# eRIC_breakout.net
KiCad netlist of a schematic drawn in EAGLE
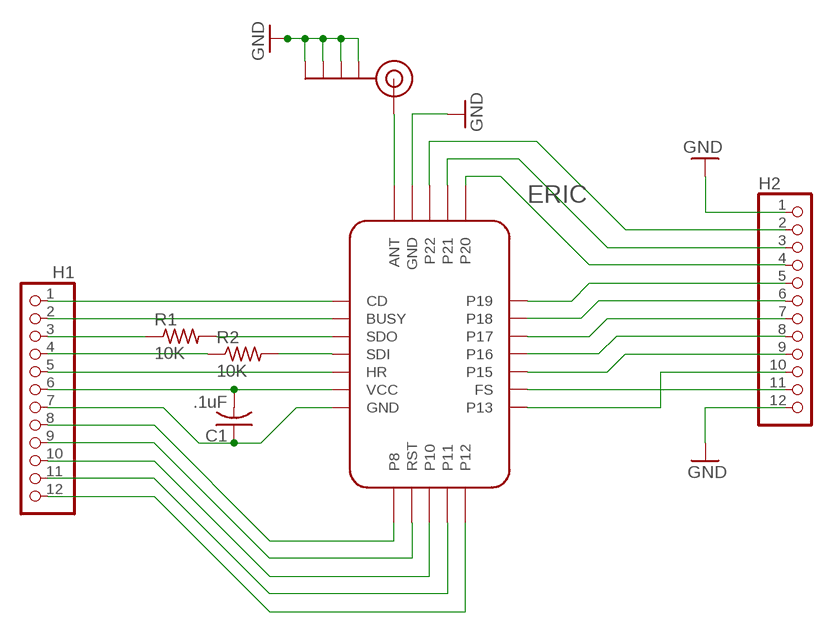
[diagram p0: schematic, sheet 1]

(export (version "E")
  (design (tool "Eeschema 10.0.6"))
  (components
    (comp (ref "C1")
      (value ".1uF")
      (footprint "eagle-import:C0603K")
      (libsource (lib "eagle-import") (part "C-USC0603K"))
    )
    (comp (ref "ERIC")
      (value "ERIC")
      (footprint "eagle-import:ERIC")
      (libsource (lib "eagle-import") (part "ERIC"))
    )
    (comp (ref "H1")
      (value "PINHD-1X12-CB")
      (footprint "eagle-import:1X12-CB")
      (libsource (lib "eagle-import") (part "PINHD-1X12-CB"))
    )
    (comp (ref "H2")
      (value "PINHD-1X12-CB")
      (footprint "eagle-import:1X12-CB")
      (libsource (lib "eagle-import") (part "PINHD-1X12-CB"))
    )
    (comp (ref "J$1")
      (value "SMA_EDGE")
      (footprint "eagle-import:SMA-EDGE")
      (libsource (lib "eagle-import") (part "SMA_EDGE"))
    )
    (comp (ref "R1")
      (value "10K")
      (footprint "eagle-import:R0603")
      (libsource (lib "eagle-import") (part "R-US_R0603"))
    )
    (comp (ref "R2")
      (value "10K")
      (footprint "eagle-import:R0603")
      (libsource (lib "eagle-import") (part "R-US_R0603"))
    )
  )
  (nets
    (net (code "1") (name "/SDI") (class "Default")
      (node (ref "ERIC") (pin "SDI") (pinfunction "SDI_SDI") (pintype "bidirectional"))
      (node (ref "H1") (pin "4") (pinfunction "4_4") (pintype "passive"))
      (node (ref "R2") (pin "1") (pinfunction "1_1") (pintype "passive"))
      (node (ref "R2") (pin "2") (pinfunction "2_2") (pintype "passive"))
    )
    (net (code "2") (name "/SDO") (class "Default")
      (node (ref "ERIC") (pin "SDO") (pinfunction "SDO_SDO") (pintype "bidirectional"))
      (node (ref "H1") (pin "3") (pinfunction "3_3") (pintype "passive"))
      (node (ref "R1") (pin "1") (pinfunction "1_1") (pintype "passive"))
      (node (ref "R1") (pin "2") (pinfunction "2_2") (pintype "passive"))
    )
    (net (code "3") (name "GND") (class "Default")
      (node (ref "C1") (pin "1") (pinfunction "1_1") (pintype "passive"))
      (node (ref "ERIC") (pin "AGND") (pinfunction "GND_AGND") (pintype "bidirectional"))
      (node (ref "ERIC") (pin "GND") (pinfunction "GND_GND") (pintype "power_in"))
      (node (ref "H1") (pin "7") (pinfunction "7_7") (pintype "passive"))
      (node (ref "H2") (pin "1") (pinfunction "1_1") (pintype "passive"))
      (node (ref "H2") (pin "12") (pinfunction "12_12") (pintype "passive"))
      (node (ref "J$1") (pin "GND@0") (pinfunction "GND_GND@0") (pintype "bidirectional"))
      (node (ref "J$1") (pin "GND@1") (pinfunction "GND_GND@1") (pintype "bidirectional"))
      (node (ref "J$1") (pin "GND@2") (pinfunction "GND_GND@2") (pintype "bidirectional"))
      (node (ref "J$1") (pin "GND@3") (pinfunction "GND_GND@3") (pintype "bidirectional"))
    )
    (net (code "4") (name "Net-(C1-Pad2)") (class "Default")
      (node (ref "C1") (pin "2") (pinfunction "2_2") (pintype "passive"))
      (node (ref "ERIC") (pin "VCC") (pinfunction "VCC_VCC") (pintype "power_in"))
      (node (ref "H1") (pin "6") (pinfunction "6_6") (pintype "passive"))
    )
    (net (code "5") (name "Net-(ERIC-P8)") (class "Default")
      (node (ref "ERIC") (pin "E8") (pinfunction "P8_E8") (pintype "bidirectional"))
      (node (ref "H1") (pin "8") (pinfunction "8_8") (pintype "passive"))
    )
    (net (code "6") (name "Net-(ERIC-P10)") (class "Default")
      (node (ref "ERIC") (pin "E10") (pinfunction "P10_E10") (pintype "bidirectional"))
      (node (ref "H1") (pin "10") (pinfunction "10_10") (pintype "passive"))
    )
    (net (code "7") (name "Net-(ERIC-P11)") (class "Default")
      (node (ref "ERIC") (pin "E11") (pinfunction "P11_E11") (pintype "bidirectional"))
      (node (ref "H1") (pin "11") (pinfunction "11_11") (pintype "passive"))
    )
    (net (code "8") (name "Net-(ERIC-P12)") (class "Default")
      (node (ref "ERIC") (pin "E12") (pinfunction "P12_E12") (pintype "bidirectional"))
      (node (ref "H1") (pin "12") (pinfunction "12_12") (pintype "passive"))
    )
    (net (code "9") (name "Net-(ERIC-P13)") (class "Default")
      (node (ref "ERIC") (pin "E13") (pinfunction "P13_E13") (pintype "bidirectional"))
      (node (ref "H2") (pin "10") (pinfunction "10_10") (pintype "passive"))
    )
    (net (code "10") (name "Net-(ERIC-P15)") (class "Default")
      (node (ref "ERIC") (pin "E15") (pinfunction "P15_E15") (pintype "bidirectional"))
      (node (ref "H2") (pin "9") (pinfunction "9_9") (pintype "passive"))
    )
    (net (code "11") (name "Net-(ERIC-P16)") (class "Default")
      (node (ref "ERIC") (pin "E16") (pinfunction "P16_E16") (pintype "bidirectional"))
      (node (ref "H2") (pin "8") (pinfunction "8_8") (pintype "passive"))
    )
    (net (code "12") (name "Net-(ERIC-P17)") (class "Default")
      (node (ref "ERIC") (pin "E17") (pinfunction "P17_E17") (pintype "bidirectional"))
      (node (ref "H2") (pin "7") (pinfunction "7_7") (pintype "passive"))
    )
    (net (code "13") (name "Net-(ERIC-P18)") (class "Default")
      (node (ref "ERIC") (pin "E18") (pinfunction "P18_E18") (pintype "bidirectional"))
      (node (ref "H2") (pin "6") (pinfunction "6_6") (pintype "passive"))
    )
    (net (code "14") (name "Net-(ERIC-P19)") (class "Default")
      (node (ref "ERIC") (pin "E19") (pinfunction "P19_E19") (pintype "bidirectional"))
      (node (ref "H2") (pin "5") (pinfunction "5_5") (pintype "passive"))
    )
    (net (code "15") (name "Net-(ERIC-P20)") (class "Default")
      (node (ref "ERIC") (pin "E20") (pinfunction "P20_E20") (pintype "bidirectional"))
      (node (ref "H2") (pin "4") (pinfunction "4_4") (pintype "passive"))
    )
    (net (code "16") (name "Net-(ERIC-P21)") (class "Default")
      (node (ref "ERIC") (pin "E21") (pinfunction "P21_E21") (pintype "bidirectional"))
      (node (ref "H2") (pin "3") (pinfunction "3_3") (pintype "passive"))
    )
    (net (code "17") (name "Net-(ERIC-P22)") (class "Default")
      (node (ref "ERIC") (pin "E22") (pinfunction "P22_E22") (pintype "bidirectional"))
      (node (ref "H2") (pin "2") (pinfunction "2_2") (pintype "passive"))
    )
    (net (code "18") (name "Net-(ERIC-PadBUSY)") (class "Default")
      (node (ref "ERIC") (pin "BUSY") (pinfunction "BUSY_BUSY") (pintype "bidirectional"))
      (node (ref "H1") (pin "2") (pinfunction "2_2") (pintype "passive"))
    )
    (net (code "19") (name "Net-(ERIC-PadCD)") (class "Default")
      (node (ref "ERIC") (pin "CD") (pinfunction "CD_CD") (pintype "bidirectional"))
      (node (ref "H1") (pin "1") (pinfunction "1_1") (pintype "passive"))
    )
    (net (code "20") (name "Net-(ERIC-PadFS)") (class "Default")
      (node (ref "ERIC") (pin "FS") (pinfunction "FS_FS") (pintype "bidirectional"))
      (node (ref "H2") (pin "11") (pinfunction "11_11") (pintype "passive"))
    )
    (net (code "21") (name "Net-(ERIC-PadHR)") (class "Default")
      (node (ref "ERIC") (pin "HR") (pinfunction "HR_HR") (pintype "bidirectional"))
      (node (ref "H1") (pin "5") (pinfunction "5_5") (pintype "passive"))
    )
    (net (code "22") (name "Net-(ERIC-RST)") (class "Default")
      (node (ref "ERIC") (pin "E9") (pinfunction "RST_E9") (pintype "bidirectional"))
      (node (ref "H1") (pin "9") (pinfunction "9_9") (pintype "passive"))
    )
    (net (code "23") (name "Net-(J$1-SIGNAL)") (class "Default")
      (node (ref "ERIC") (pin "ANT") (pinfunction "ANT_ANT") (pintype "bidirectional"))
      (node (ref "J$1") (pin "SIG") (pinfunction "SIGNAL_SIG") (pintype "bidirectional"))
    )
  )
)
